# HYDRA_V4_POWER.net
KiCad netlist of a schematic drawn in Altium Designer
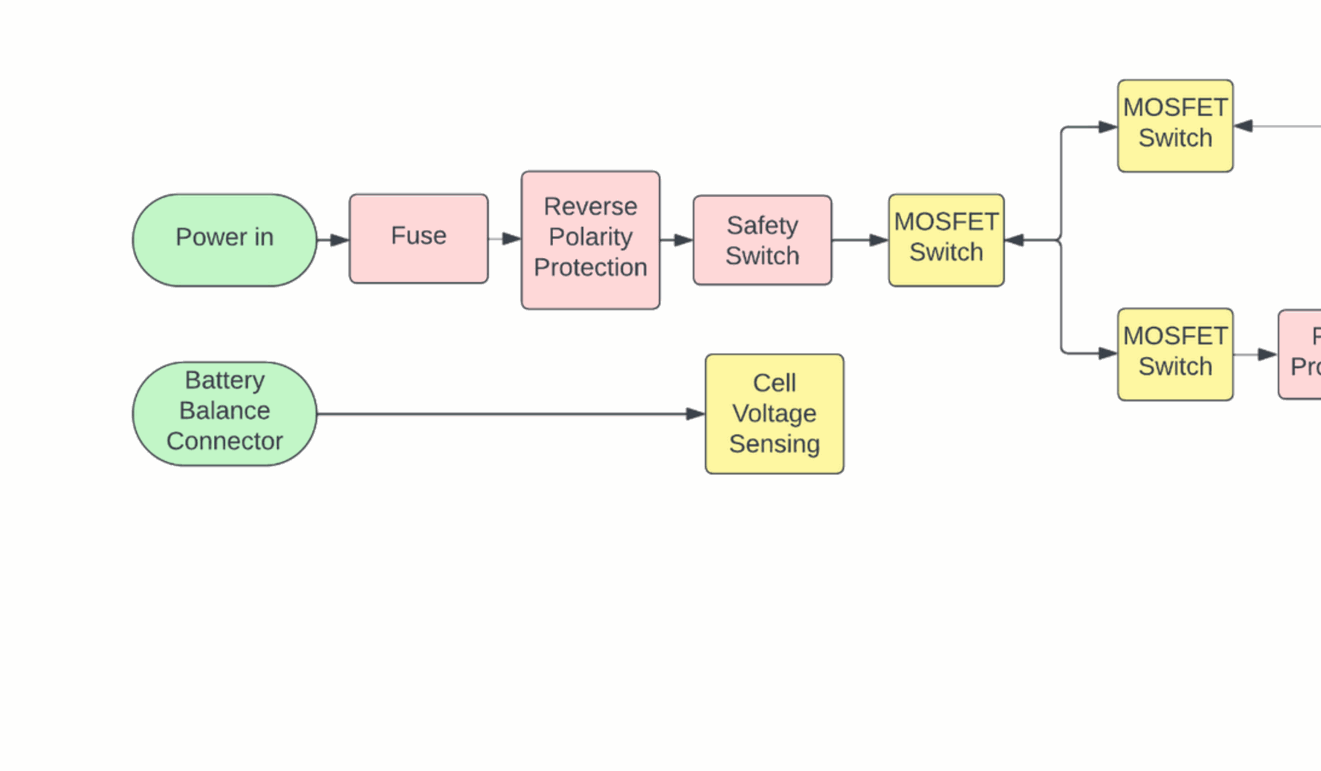
[diagram p0: HYDRA_V4_POWER.SchDoc, top left]
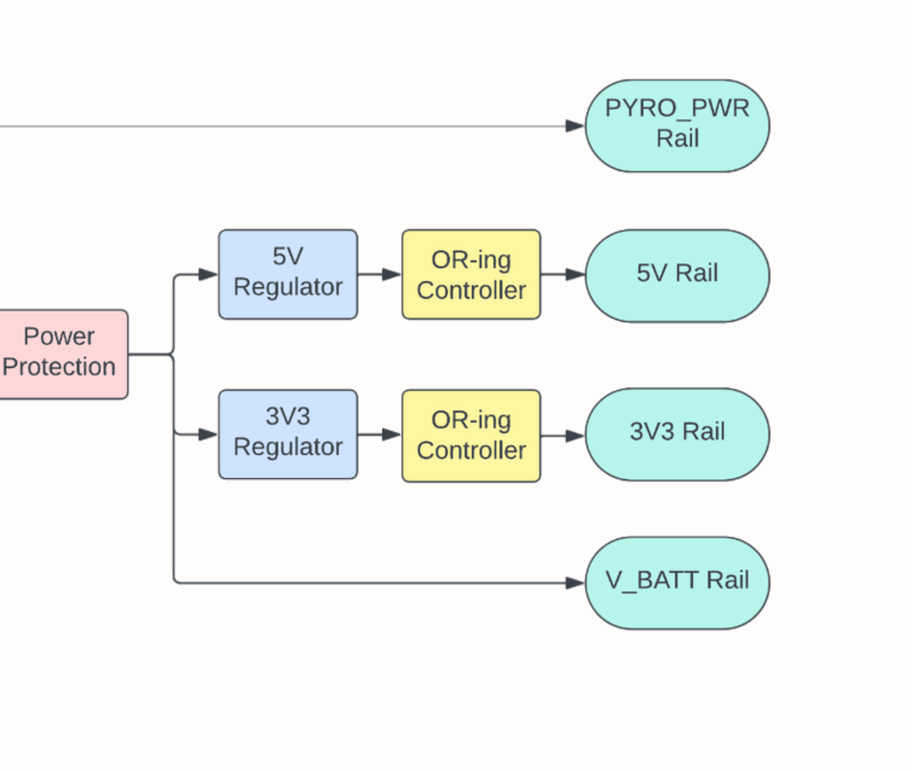
[diagram p1: HYDRA_V4_POWER.SchDoc, top right]
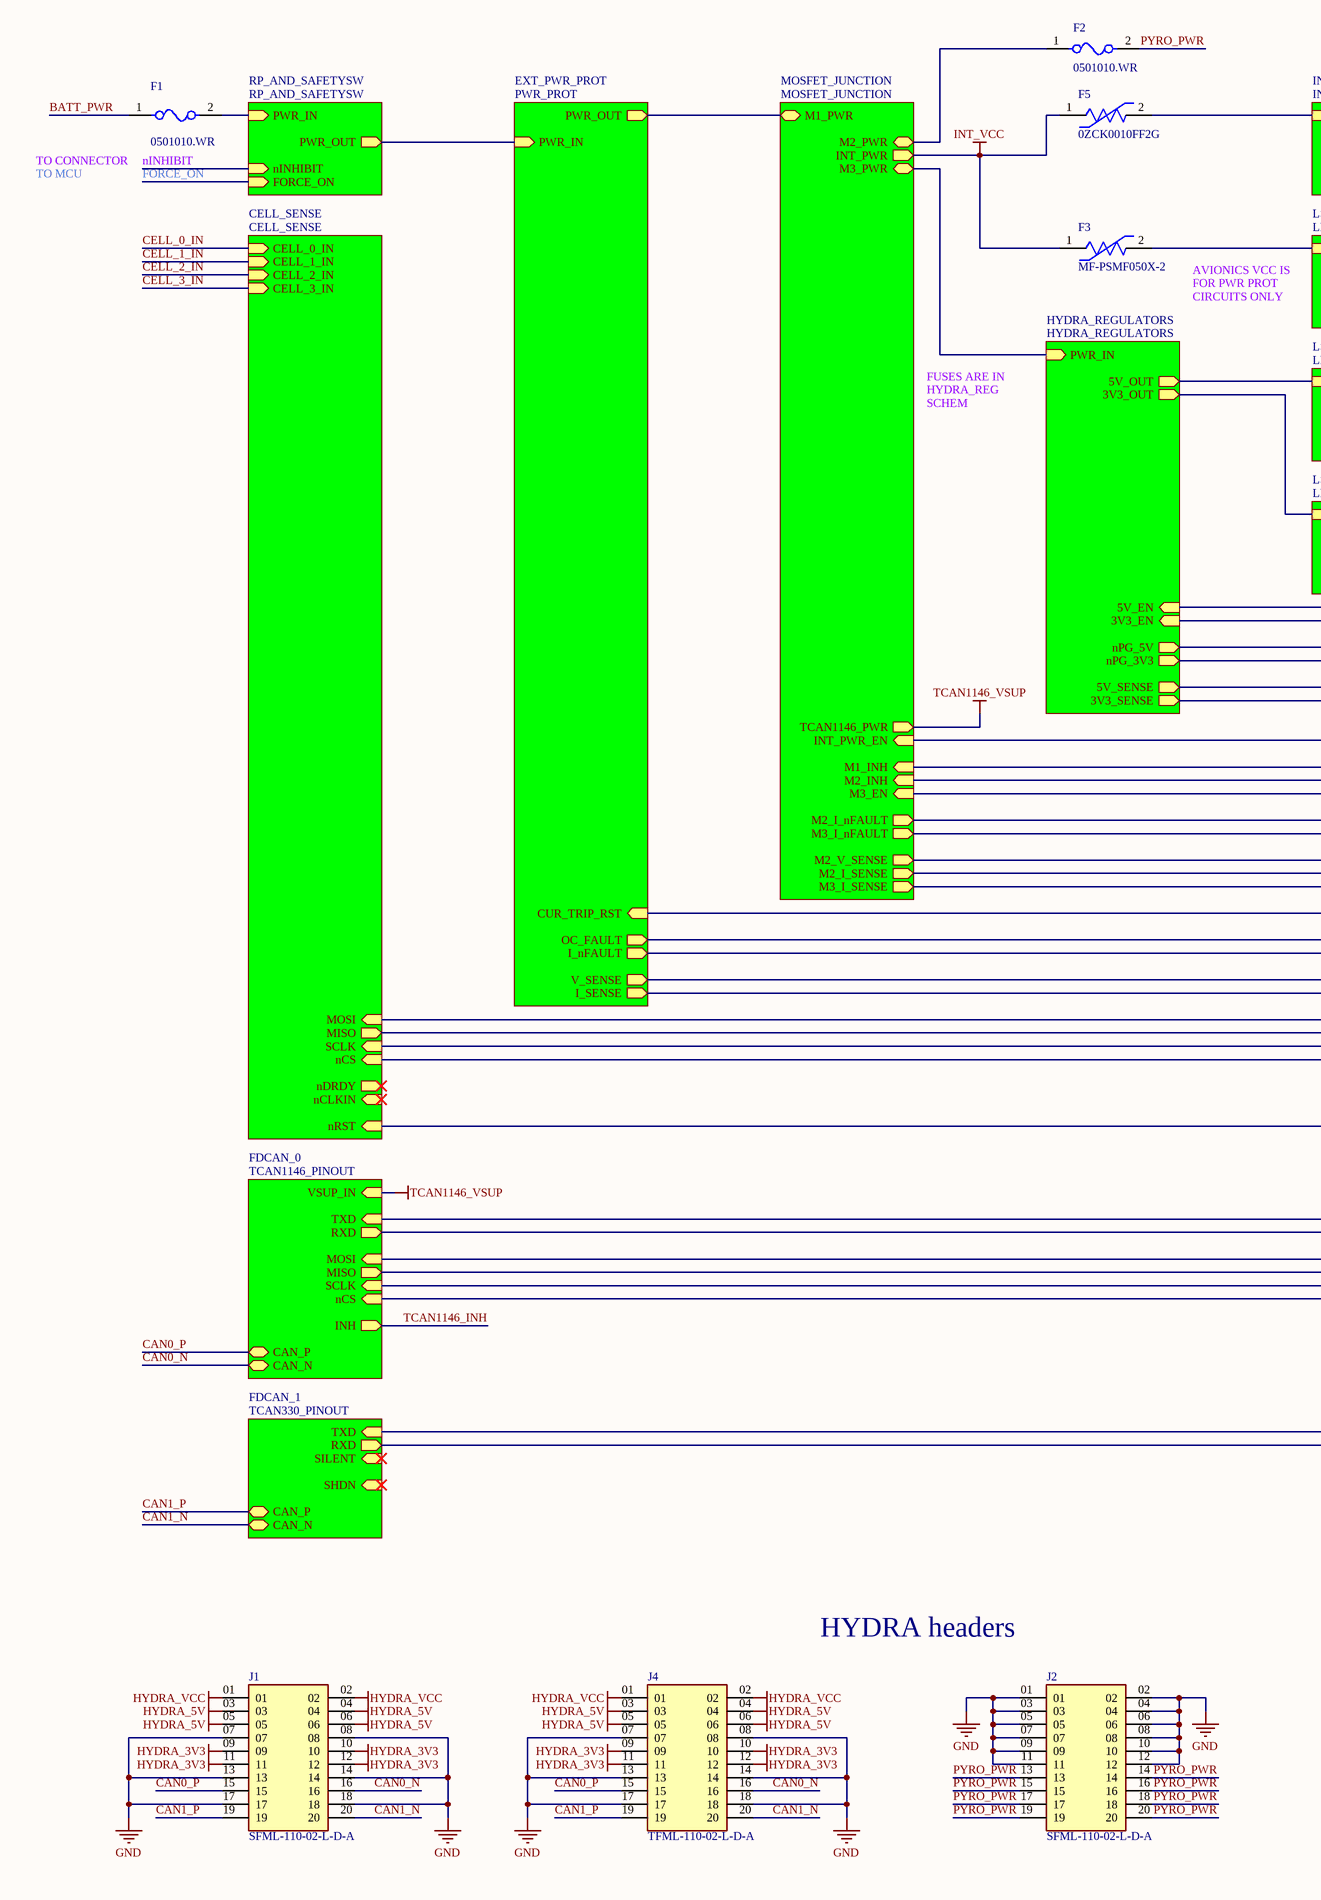
[diagram p2: HYDRA_V4_POWER.SchDoc, bottom left]
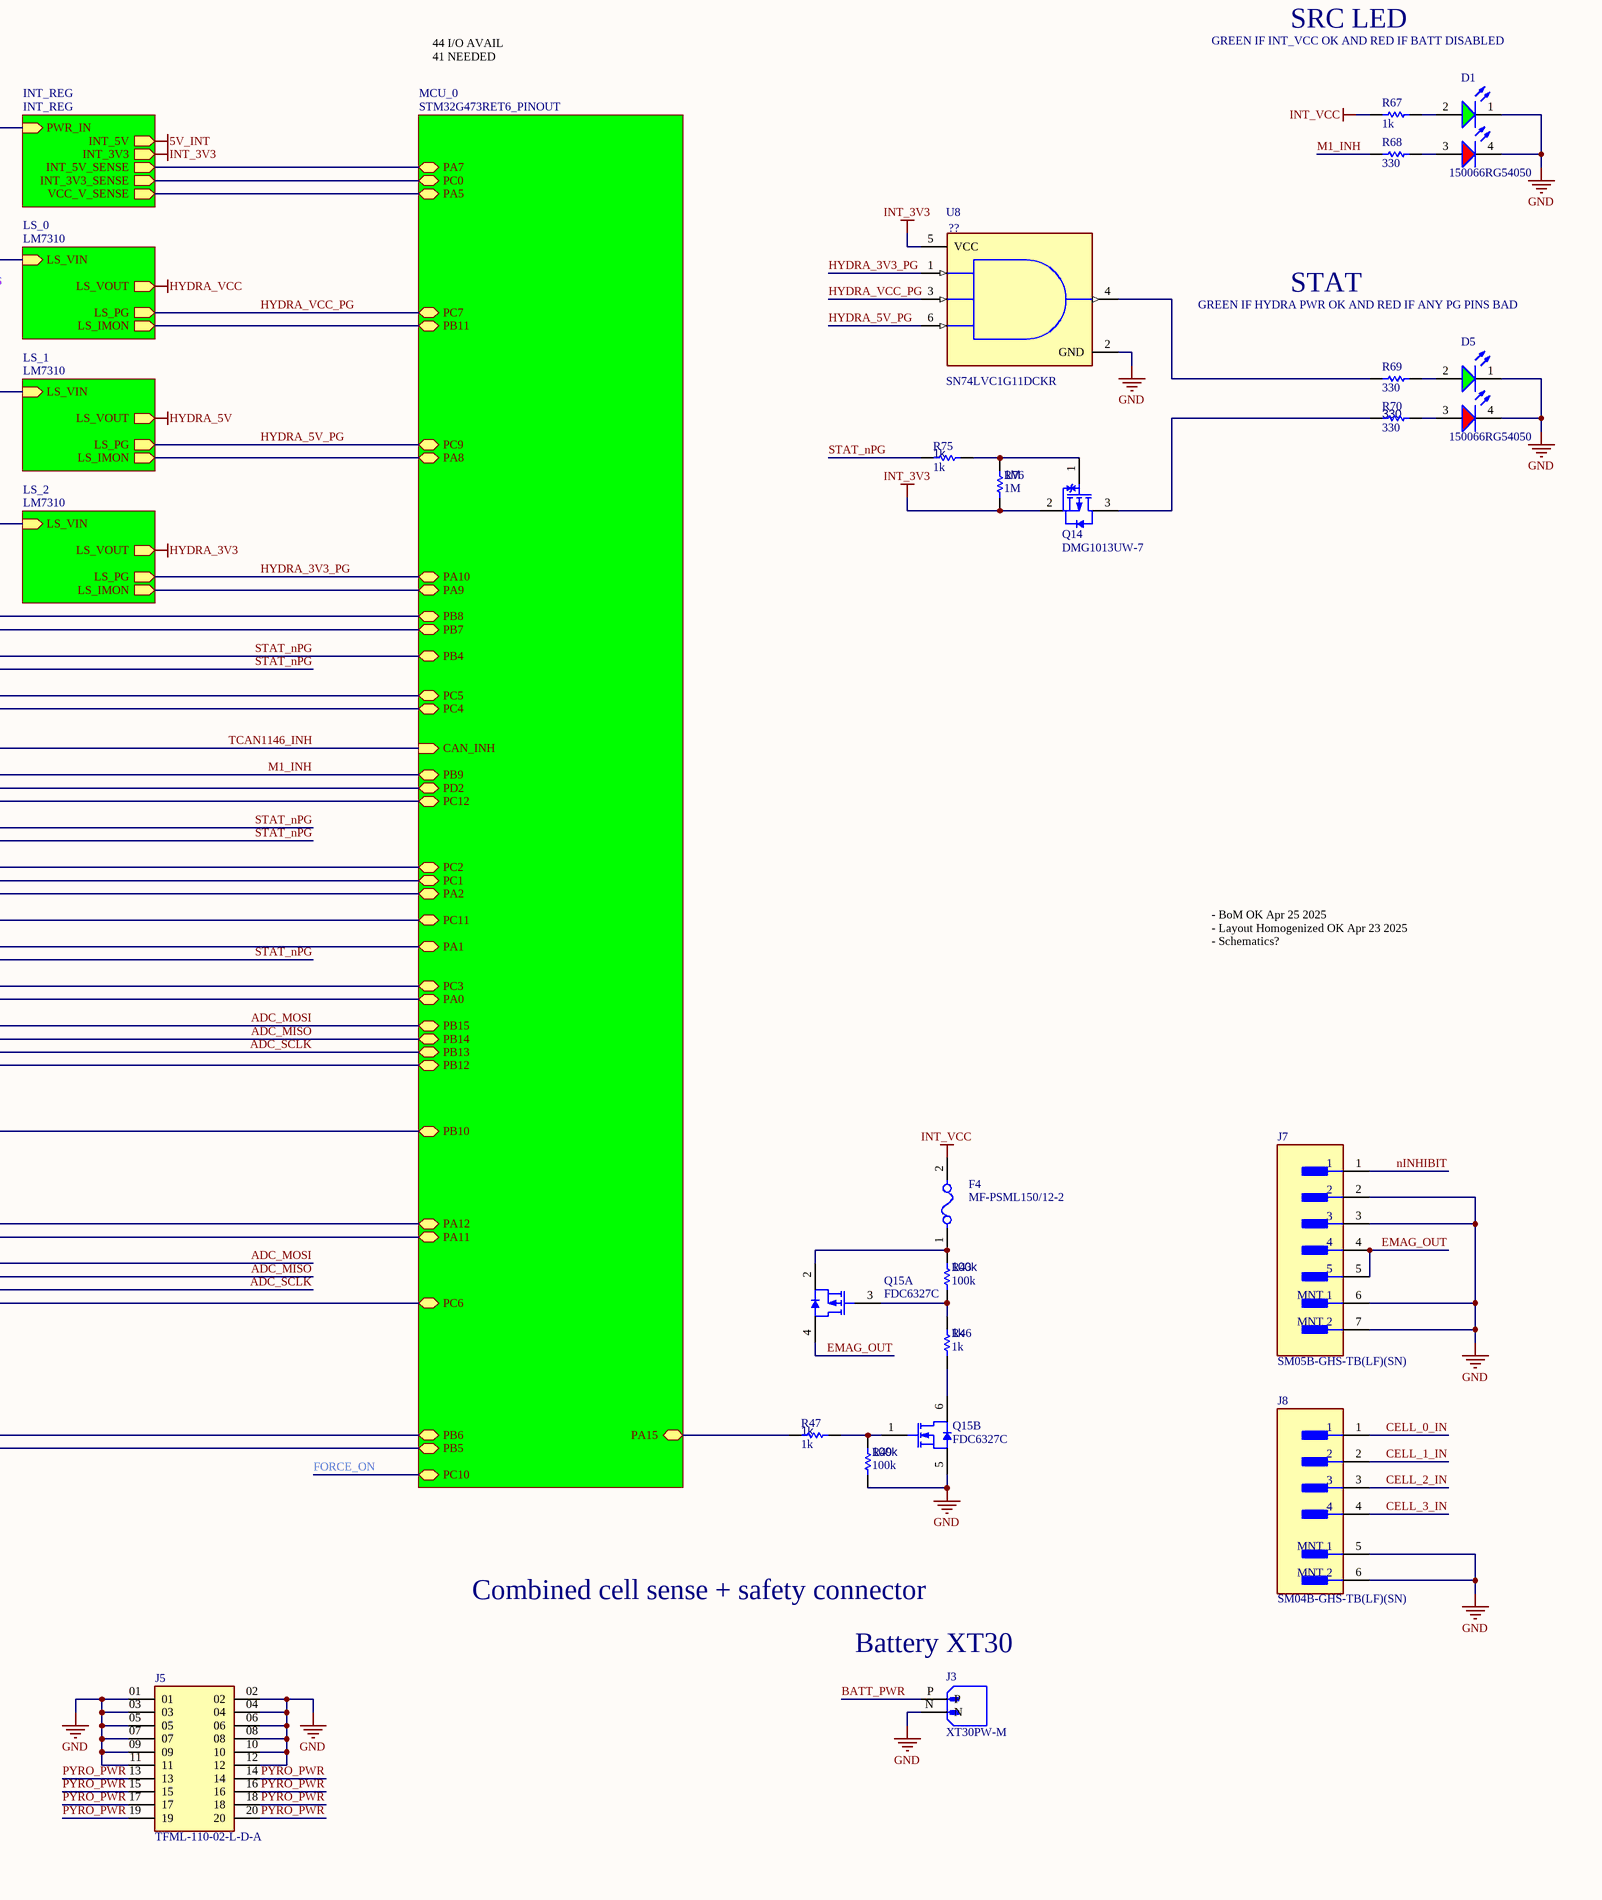
[diagram p3: HYDRA_V4_POWER.SchDoc, bottom right]

(export (version "E")
  (design (tool "Eeschema 10.0.6"))
  (components
    (comp (ref "D1")
      (value "150066RG54050")
      (footprint "WL-SBCD_0606")
      (description "Led, Red/Grn, 180Mcd/230Mcd, 624Nm/525Nm Rohs Compliant: Yes")
      (fields (field (name "SOURCE") "rgled.SchLib"))
      (libsource (lib "Space Concordia") (part "CMP-004-00034-2"))
    )
    (comp (ref "D5")
      (value "150066RG54050")
      (footprint "WL-SBCD_0606")
      (description "Led, Red/Grn, 180Mcd/230Mcd, 624Nm/525Nm Rohs Compliant: Yes")
      (fields (field (name "SOURCE") "rgled.SchLib"))
      (libsource (lib "Space Concordia") (part "CMP-004-00034-2"))
    )
    (comp (ref "F1")
      (value "0501010.WR")
      (footprint "FP-0501-MFG")
      (description "FUSE BOARD MOUNT 10A 32VDC 1206")
      (libsource (lib "Altium Content Vault") (part "5bcf9b9f640e542cf0359d10258e979"))
    )
    (comp (ref "F2")
      (value "0501010.WR")
      (footprint "FP-0501-MFG")
      (description "FUSE BOARD MOUNT 10A 32VDC 1206")
      (libsource (lib "Altium Content Vault") (part "5bcf9b9f640e542cf0359d10258e979"))
    )
    (comp (ref "F3")
      (value "MF-PSMF050X-2")
      (footprint "FP-MF-PSMF-MFG")
      (description "PTC RESET FUSE 6V 500MA 0805")
      (fields
        (field (name "MANUFACTURER") "Bourns Inc.")
        (field (name "OCTOPART") "https://octopart.com/mf-psmf050x-2-bourns-7483438")
      )
      (libsource (lib "Altium Content Vault") (part "fdf083d5f6389a9a1c4e51137f46658"))
    )
    (comp (ref "F4")
      (value "MF-PSML150/12-2")
      (footprint "FP-0805L010-MFG")
      (libsource (lib "Altium Content Vault") (part "5bcf9b9f640e542cf0359d10258e979"))
    )
    (comp (ref "F5")
      (value "0ZCK0010FF2G")
      (footprint "FP-0ZCK0010FF2G-MFG")
      (description "PTC RESET FUSE 15V 100MA 0805")
      (libsource (lib "Altium Content Vault") (part "fc31388045fc42ab786d6d00b506e9f"))
    )
    (comp (ref "J1")
      (value "SFML-110-02-L-D-A")
      (footprint "SFML-110-02-L-D-A-Footprint-1")
      (libsource (lib "Space Concordia") (part "SFML-110-02-L-D-A"))
    )
    (comp (ref "J2")
      (value "SFML-110-02-L-D-A")
      (footprint "SFML-110-02-L-D-A-Footprint-1")
      (libsource (lib "Space Concordia") (part "SFML-110-02-L-D-A"))
    )
    (comp (ref "J3")
      (value "XT30PW-M")
      (footprint "XT30PW-M-Footprint-1")
      (libsource (lib "Space Concordia") (part "XT30PW-M"))
    )
    (comp (ref "J4")
      (value "TFML-110-02-L-D-A")
      (footprint "TFML-110-02-L-D-A-Footprint-1")
      (description "Board Connector, 20 Contact(s), 2 Row(s), Male, Straight, Surface Mount Terminal")
      (libsource (lib "Space Concordia") (part "TFML-110-02-L-D-A"))
    )
    (comp (ref "J5")
      (value "TFML-110-02-L-D-A")
      (footprint "TFML-110-02-L-D-A-Footprint-1")
      (description "Board Connector, 20 Contact(s), 2 Row(s), Male, Straight, Surface Mount Terminal")
      (libsource (lib "Space Concordia") (part "TFML-110-02-L-D-A"))
    )
    (comp (ref "J7")
      (value "SM05B-GHS-TB(LF)(SN)")
      (footprint "FP-SM05B-GHS-TB_LF_SN-MFG")
      (description "Connector Header, GH Series, 5 Position, 1.25mm, Surface Mount, Right Angle, Tin, Natural")
      (libsource (lib "Space Concordia") (part "8ab9848ea90b119fa28a5ddc5abf419"))
    )
    (comp (ref "J8")
      (value "SM04B-GHS-TB(LF)(SN)")
      (footprint "FP-SM04B-GHS-TB_LF_SN-MFG")
      (description "Conn Shrouded Header HDR 4 POS 1.25mm Solder RA SMD Reel")
      (libsource (lib "Space Concordia") (part "f4320a1371cd6270e33bce1916c33c0"))
    )
    (comp (ref "Q14")
      (value "DMG1013UW-7")
      (footprint "DIOD-SOT323-3_V")
      (fields (field (name "MANUFACTURER") "Diodes Inc"))
      (libsource (lib "Altium Content Vault") (part "PEMOS-GSD-3_C"))
    )
    (comp (ref "Q15")
      (value "FDC6327C")
      (footprint "FAIR-SOT23-6_V")
      (fields (field (name "MANUFACTURER") "Fairchild"))
      (libsource (lib "Altium Content Vault") (part "PEMOS-SGD-NEMOS-GSD-6"))
    )
    (comp (ref "R43")
      (value "100k")
      (footprint "R0603B")
      (description "Resistor")
      (fields (field (name "ALTIUM_VALUE") "100k"))
      (libsource (lib "Space Concordia") (part "Resistor"))
    )
    (comp (ref "R46")
      (value "1k")
      (footprint "R0603B")
      (description "Resistor")
      (fields (field (name "ALTIUM_VALUE") "1k"))
      (libsource (lib "Space Concordia") (part "Resistor"))
    )
    (comp (ref "R47")
      (value "1k")
      (footprint "R0603B")
      (description "Resistor")
      (fields (field (name "ALTIUM_VALUE") "1k"))
      (libsource (lib "Space Concordia") (part "Resistor"))
    )
    (comp (ref "R49")
      (value "100k")
      (footprint "R0603B")
      (description "Resistor")
      (fields (field (name "ALTIUM_VALUE") "100k"))
      (libsource (lib "Space Concordia") (part "Resistor"))
    )
    (comp (ref "R67")
      (value "1k")
      (footprint "R0603B")
      (description "Resistor")
      (libsource (lib "Space Concordia") (part "Resistor"))
    )
    (comp (ref "R68")
      (value "330")
      (footprint "R0603B")
      (description "Resistor")
      (libsource (lib "Space Concordia") (part "Resistor"))
    )
    (comp (ref "R69")
      (value "330")
      (footprint "R0603B")
      (description "Resistor")
      (libsource (lib "Space Concordia") (part "Resistor"))
    )
    (comp (ref "R70")
      (value "330")
      (footprint "R0603B")
      (description "Resistor")
      (fields (field (name "ALTIUM_VALUE") "330"))
      (libsource (lib "Space Concordia") (part "Resistor"))
    )
    (comp (ref "R75")
      (value "1k")
      (footprint "R0603B")
      (description "Resistor")
      (fields (field (name "ALTIUM_VALUE") "1k"))
      (libsource (lib "Space Concordia") (part "Resistor"))
    )
    (comp (ref "R76")
      (value "1M")
      (footprint "R0603B")
      (description "Resistor")
      (fields (field (name "ALTIUM_VALUE") "1M"))
      (libsource (lib "Space Concordia") (part "Resistor"))
    )
    (comp (ref "U8")
      (value "SN74LVC1G11DCKR")
      (footprint "FP-DCK0006A-MFG")
      (description "IC GATE AND 1CH 3-INP SC70-6")
      (fields
        (field (name "OCTOPART") "https://octopart.com/sn74lvc1g11dckr-texas+instruments-464959")
        (field (name "MANUFACTURER") "Texas Instruments")
      )
      (libsource (lib "Altium Content Vault") (part "7b84a2e0de1424f87845933602e765c"))
    )
  )
  (nets
    (net (code "10") (name "/BATT_PWR") (class "Default")
      (node (ref "F1") (pin "1") (pinfunction "1_1") (pintype "passive"))
      (node (ref "J3") (pin "P") (pinfunction "P_P") (pintype "power_in"))
    )
    (net (code "11") (name "/CAN0_N") (class "Default")
      (node (ref "J1") (pin "16") (pinfunction "16_16") (pintype "passive"))
      (node (ref "J4") (pin "16") (pinfunction "16_16") (pintype "passive"))
    )
    (net (code "12") (name "/CAN0_P") (class "Default")
      (node (ref "J1") (pin "15") (pinfunction "15_15") (pintype "passive"))
      (node (ref "J4") (pin "15") (pinfunction "15_15") (pintype "passive"))
    )
    (net (code "13") (name "/CAN1_N") (class "Default")
      (node (ref "J1") (pin "20") (pinfunction "20_20") (pintype "passive"))
      (node (ref "J4") (pin "20") (pinfunction "20_20") (pintype "passive"))
    )
    (net (code "14") (name "/CAN1_P") (class "Default")
      (node (ref "J1") (pin "19") (pinfunction "19_19") (pintype "passive"))
      (node (ref "J4") (pin "19") (pinfunction "19_19") (pintype "passive"))
    )
    (net (code "15") (name "/CELL_0_IN") (class "Default")
      (node (ref "J8") (pin "1") (pinfunction "1_1") (pintype "passive"))
    )
    (net (code "16") (name "/CELL_1_IN") (class "Default")
      (node (ref "J8") (pin "2") (pinfunction "2_2") (pintype "passive"))
    )
    (net (code "17") (name "/CELL_2_IN") (class "Default")
      (node (ref "J8") (pin "3") (pinfunction "3_3") (pintype "passive"))
    )
    (net (code "18") (name "/CELL_3_IN") (class "Default")
      (node (ref "J8") (pin "4") (pinfunction "4_4") (pintype "passive"))
    )
    (net (code "20") (name "/EMAG_OUT") (class "Default")
      (node (ref "J7") (pin "4") (pinfunction "4_4") (pintype "passive"))
      (node (ref "J7") (pin "5") (pinfunction "5_5") (pintype "passive"))
      (node (ref "Q15") (pin "4") (pinfunction "D_4") (pintype "passive"))
    )
    (net (code "22") (name "/HYDRA_3V3_PG") (class "Default")
      (node (ref "U8") (pin "1") (pinfunction "A_1") (pintype "input"))
    )
    (net (code "23") (name "/HYDRA_5V_PG") (class "Default")
      (node (ref "U8") (pin "6") (pinfunction "C_6") (pintype "input"))
    )
    (net (code "24") (name "/HYDRA_VCC_PG") (class "Default")
      (node (ref "U8") (pin "3") (pinfunction "B_3") (pintype "input"))
    )
    (net (code "31") (name "/LS_VIN") (class "Default")
      (node (ref "F3") (pin "2") (pinfunction "2_2") (pintype "passive"))
    )
    (net (code "32") (name "/M1_INH") (class "Default")
      (node (ref "R68") (pin "2") (pinfunction "2_2") (pintype "passive"))
    )
    (net (code "35") (name "/M2_PWR") (class "Default")
      (node (ref "F2") (pin "1") (pinfunction "1_1") (pintype "passive"))
    )
    (net (code "42") (name "/PA15") (class "Default")
      (node (ref "R47") (pin "2") (pinfunction "2_2") (pintype "passive"))
    )
    (net (code "47") (name "/PWR_IN") (class "Default")
      (node (ref "F5") (pin "2") (pinfunction "2_2") (pintype "passive"))
    )
    (net (code "48") (name "/PWR_IN_1") (class "Default")
      (node (ref "F1") (pin "2") (pinfunction "2_2") (pintype "passive"))
    )
    (net (code "51") (name "/PYRO_PWR") (class "Default")
      (node (ref "F2") (pin "2") (pinfunction "2_2") (pintype "passive"))
      (node (ref "J2") (pin "13") (pinfunction "13_13") (pintype "passive"))
      (node (ref "J2") (pin "14") (pinfunction "14_14") (pintype "passive"))
      (node (ref "J2") (pin "15") (pinfunction "15_15") (pintype "passive"))
      (node (ref "J2") (pin "16") (pinfunction "16_16") (pintype "passive"))
      (node (ref "J2") (pin "17") (pinfunction "17_17") (pintype "passive"))
      (node (ref "J2") (pin "18") (pinfunction "18_18") (pintype "passive"))
      (node (ref "J2") (pin "19") (pinfunction "19_19") (pintype "passive"))
      (node (ref "J2") (pin "20") (pinfunction "20_20") (pintype "passive"))
      (node (ref "J5") (pin "13") (pinfunction "13_13") (pintype "passive"))
      (node (ref "J5") (pin "14") (pinfunction "14_14") (pintype "passive"))
      (node (ref "J5") (pin "15") (pinfunction "15_15") (pintype "passive"))
      (node (ref "J5") (pin "16") (pinfunction "16_16") (pintype "passive"))
      (node (ref "J5") (pin "17") (pinfunction "17_17") (pintype "passive"))
      (node (ref "J5") (pin "18") (pinfunction "18_18") (pintype "passive"))
      (node (ref "J5") (pin "19") (pinfunction "19_19") (pintype "passive"))
      (node (ref "J5") (pin "20") (pinfunction "20_20") (pintype "passive"))
    )
    (net (code "56") (name "/STAT_nPG") (class "Default")
      (node (ref "R75") (pin "2") (pinfunction "2_2") (pintype "passive"))
    )
    (net (code "62") (name "/nINHIBIT") (class "Default")
      (node (ref "J7") (pin "1") (pinfunction "1_1") (pintype "passive"))
    )
    (net (code "64") (name "GND") (class "Default")
      (node (ref "D1") (pin "1") (pinfunction "K_1") (pintype "passive"))
      (node (ref "D1") (pin "4") (pinfunction "K_4") (pintype "passive"))
      (node (ref "D5") (pin "1") (pinfunction "K_1") (pintype "passive"))
      (node (ref "D5") (pin "4") (pinfunction "K_4") (pintype "passive"))
      (node (ref "J1") (pin "07") (pinfunction "07_07") (pintype "passive"))
      (node (ref "J1") (pin "08") (pinfunction "08_08") (pintype "passive"))
      (node (ref "J1") (pin "13") (pinfunction "13_13") (pintype "passive"))
      (node (ref "J1") (pin "14") (pinfunction "14_14") (pintype "passive"))
      (node (ref "J1") (pin "17") (pinfunction "17_17") (pintype "passive"))
      (node (ref "J1") (pin "18") (pinfunction "18_18") (pintype "passive"))
      (node (ref "J2") (pin "01") (pinfunction "01_01") (pintype "passive"))
      (node (ref "J2") (pin "02") (pinfunction "02_02") (pintype "passive"))
      (node (ref "J2") (pin "03") (pinfunction "03_03") (pintype "passive"))
      (node (ref "J2") (pin "04") (pinfunction "04_04") (pintype "passive"))
      (node (ref "J2") (pin "05") (pinfunction "05_05") (pintype "passive"))
      (node (ref "J2") (pin "06") (pinfunction "06_06") (pintype "passive"))
      (node (ref "J2") (pin "07") (pinfunction "07_07") (pintype "passive"))
      (node (ref "J2") (pin "08") (pinfunction "08_08") (pintype "passive"))
      (node (ref "J2") (pin "09") (pinfunction "09_09") (pintype "passive"))
      (node (ref "J2") (pin "10") (pinfunction "10_10") (pintype "passive"))
      (node (ref "J2") (pin "11") (pinfunction "11_11") (pintype "passive"))
      (node (ref "J2") (pin "12") (pinfunction "12_12") (pintype "passive"))
      (node (ref "J3") (pin "N") (pinfunction "N_N") (pintype "power_in"))
      (node (ref "J4") (pin "07") (pinfunction "07_07") (pintype "passive"))
      (node (ref "J4") (pin "08") (pinfunction "08_08") (pintype "passive"))
      (node (ref "J4") (pin "13") (pinfunction "13_13") (pintype "passive"))
      (node (ref "J4") (pin "14") (pinfunction "14_14") (pintype "passive"))
      (node (ref "J4") (pin "17") (pinfunction "17_17") (pintype "passive"))
      (node (ref "J4") (pin "18") (pinfunction "18_18") (pintype "passive"))
      (node (ref "J5") (pin "01") (pinfunction "01_01") (pintype "passive"))
      (node (ref "J5") (pin "02") (pinfunction "02_02") (pintype "passive"))
      (node (ref "J5") (pin "03") (pinfunction "03_03") (pintype "passive"))
      (node (ref "J5") (pin "04") (pinfunction "04_04") (pintype "passive"))
      (node (ref "J5") (pin "05") (pinfunction "05_05") (pintype "passive"))
      (node (ref "J5") (pin "06") (pinfunction "06_06") (pintype "passive"))
      (node (ref "J5") (pin "07") (pinfunction "07_07") (pintype "passive"))
      (node (ref "J5") (pin "08") (pinfunction "08_08") (pintype "passive"))
      (node (ref "J5") (pin "09") (pinfunction "09_09") (pintype "passive"))
      (node (ref "J5") (pin "10") (pinfunction "10_10") (pintype "passive"))
      (node (ref "J5") (pin "11") (pinfunction "11_11") (pintype "passive"))
      (node (ref "J5") (pin "12") (pinfunction "12_12") (pintype "passive"))
      (node (ref "J7") (pin "2") (pinfunction "2_2") (pintype "passive"))
      (node (ref "J7") (pin "3") (pinfunction "3_3") (pintype "passive"))
      (node (ref "J7") (pin "6") (pinfunction "MNT_1_6") (pintype "passive"))
      (node (ref "J7") (pin "7") (pinfunction "MNT_2_7") (pintype "passive"))
      (node (ref "J8") (pin "5") (pinfunction "MNT_1_5") (pintype "passive"))
      (node (ref "J8") (pin "6") (pinfunction "MNT_2_6") (pintype "passive"))
      (node (ref "Q15") (pin "5") (pinfunction "S_5") (pintype "passive"))
      (node (ref "R49") (pin "2") (pinfunction "2_2") (pintype "passive"))
      (node (ref "U8") (pin "2") (pinfunction "GND_2") (pintype "power_in"))
    )
    (net (code "65") (name "HYDRA_3V3") (class "Default")
      (node (ref "J1") (pin "09") (pinfunction "09_09") (pintype "passive"))
      (node (ref "J1") (pin "10") (pinfunction "10_10") (pintype "passive"))
      (node (ref "J1") (pin "11") (pinfunction "11_11") (pintype "passive"))
      (node (ref "J1") (pin "12") (pinfunction "12_12") (pintype "passive"))
      (node (ref "J4") (pin "09") (pinfunction "09_09") (pintype "passive"))
      (node (ref "J4") (pin "10") (pinfunction "10_10") (pintype "passive"))
      (node (ref "J4") (pin "11") (pinfunction "11_11") (pintype "passive"))
      (node (ref "J4") (pin "12") (pinfunction "12_12") (pintype "passive"))
    )
    (net (code "66") (name "HYDRA_5V") (class "Default")
      (node (ref "J1") (pin "03") (pinfunction "03_03") (pintype "passive"))
      (node (ref "J1") (pin "04") (pinfunction "04_04") (pintype "passive"))
      (node (ref "J1") (pin "05") (pinfunction "05_05") (pintype "passive"))
      (node (ref "J1") (pin "06") (pinfunction "06_06") (pintype "passive"))
      (node (ref "J4") (pin "03") (pinfunction "03_03") (pintype "passive"))
      (node (ref "J4") (pin "04") (pinfunction "04_04") (pintype "passive"))
      (node (ref "J4") (pin "05") (pinfunction "05_05") (pintype "passive"))
      (node (ref "J4") (pin "06") (pinfunction "06_06") (pintype "passive"))
    )
    (net (code "67") (name "HYDRA_VCC") (class "Default")
      (node (ref "J1") (pin "01") (pinfunction "01_01") (pintype "passive"))
      (node (ref "J1") (pin "02") (pinfunction "02_02") (pintype "passive"))
      (node (ref "J4") (pin "01") (pinfunction "01_01") (pintype "passive"))
      (node (ref "J4") (pin "02") (pinfunction "02_02") (pintype "passive"))
    )
    (net (code "68") (name "INT_3V3") (class "Default")
      (node (ref "Q14") (pin "2") (pinfunction "S_2") (pintype "passive"))
      (node (ref "R76") (pin "2") (pinfunction "2_2") (pintype "passive"))
      (node (ref "U8") (pin "5") (pinfunction "VCC_5") (pintype "power_in"))
    )
    (net (code "69") (name "INT_VCC") (class "Default")
      (node (ref "F3") (pin "1") (pinfunction "1_1") (pintype "passive"))
      (node (ref "F4") (pin "2") (pinfunction "2_2") (pintype "passive"))
      (node (ref "F5") (pin "1") (pinfunction "1_1") (pintype "passive"))
      (node (ref "R67") (pin "2") (pinfunction "2_2") (pintype "passive"))
    )
    (net (code "70") (name "Net-(D1-A-Pad2)") (class "Default")
      (node (ref "D1") (pin "2") (pinfunction "A_2") (pintype "passive"))
      (node (ref "R67") (pin "1") (pinfunction "1_1") (pintype "passive"))
    )
    (net (code "71") (name "Net-(D1-A-Pad3)") (class "Default")
      (node (ref "D1") (pin "3") (pinfunction "A_3") (pintype "passive"))
      (node (ref "R68") (pin "1") (pinfunction "1_1") (pintype "passive"))
    )
    (net (code "72") (name "Net-(D5-A-Pad2)") (class "Default")
      (node (ref "D5") (pin "2") (pinfunction "A_2") (pintype "passive"))
      (node (ref "R69") (pin "1") (pinfunction "1_1") (pintype "passive"))
    )
    (net (code "73") (name "Net-(D5-A-Pad3)") (class "Default")
      (node (ref "D5") (pin "3") (pinfunction "A_3") (pintype "passive"))
      (node (ref "R70") (pin "1") (pinfunction "1_1") (pintype "passive"))
    )
    (net (code "74") (name "Net-(Q14-D)") (class "Default")
      (node (ref "Q14") (pin "3") (pinfunction "D_3") (pintype "passive"))
      (node (ref "R70") (pin "2") (pinfunction "2_2") (pintype "passive"))
    )
    (net (code "75") (name "Net-(Q14-G)") (class "Default")
      (node (ref "Q14") (pin "1") (pinfunction "G_1") (pintype "passive"))
      (node (ref "R75") (pin "1") (pinfunction "1_1") (pintype "passive"))
      (node (ref "R76") (pin "1") (pinfunction "1_1") (pintype "passive"))
    )
    (net (code "76") (name "Net-(Q15A-G)") (class "Default")
      (node (ref "Q15") (pin "3") (pinfunction "G_3") (pintype "passive"))
      (node (ref "R43") (pin "1") (pinfunction "1_1") (pintype "passive"))
      (node (ref "R46") (pin "1") (pinfunction "1_1") (pintype "passive"))
    )
    (net (code "77") (name "Net-(Q15A-S)") (class "Default")
      (node (ref "F4") (pin "1") (pinfunction "1_1") (pintype "passive"))
      (node (ref "Q15") (pin "2") (pinfunction "S_2") (pintype "passive"))
      (node (ref "R43") (pin "2") (pinfunction "2_2") (pintype "passive"))
    )
    (net (code "78") (name "Net-(Q15B-D)") (class "Default")
      (node (ref "Q15") (pin "6") (pinfunction "D_6") (pintype "passive"))
      (node (ref "R46") (pin "2") (pinfunction "2_2") (pintype "passive"))
    )
    (net (code "79") (name "Net-(Q15B-G)") (class "Default")
      (node (ref "Q15") (pin "1") (pinfunction "G_1") (pintype "passive"))
      (node (ref "R47") (pin "1") (pinfunction "1_1") (pintype "passive"))
      (node (ref "R49") (pin "1") (pinfunction "1_1") (pintype "passive"))
    )
    (net (code "80") (name "Net-(U8-Y)") (class "Default")
      (node (ref "R69") (pin "2") (pinfunction "2_2") (pintype "passive"))
      (node (ref "U8") (pin "4") (pinfunction "Y_4") (pintype "output"))
    )
  )
)
